# BootCircuit.net
KiCad netlist of a schematic drawn in Altium Designer
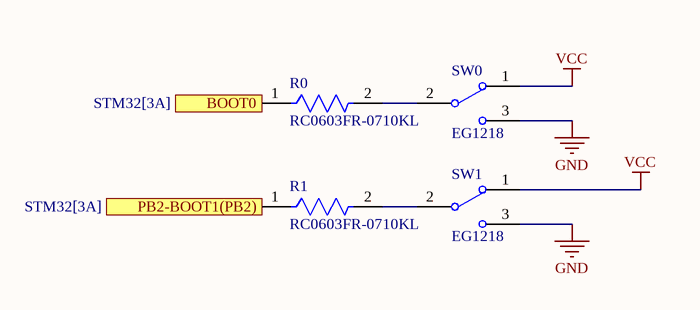
[diagram p0: BootCircuit.SchDoc]

(export (version "E")
  (design (tool "Eeschema 10.0.6"))
  (components
    (comp (ref "R0")
      (value "RC0603FR-0710KL")
      (footprint "FP-RC0603-0_55-IPC_C")
      (description "RES 10K OHM 1% 1/10W 0603")
      (fields (field (name "TOLERANCE") "1%"))
      (libsource (lib "Altium Content Vault") (part "1029c3af85768c4190bb7ad29bc67b5"))
    )
    (comp (ref "R1")
      (value "RC0603FR-0710KL")
      (footprint "FP-RC0603-0_55-IPC_C")
      (description "RES 10K OHM 1% 1/10W 0603")
      (fields (field (name "TOLERANCE") "1%"))
      (libsource (lib "Altium Content Vault") (part "1029c3af85768c4190bb7ad29bc67b5"))
    )
    (comp (ref "SW0")
      (value "EG1218")
      (footprint "ESWI-EG1218_V")
      (description "Slide Switch, 500 V, -20 to 70 degC, 3-Pin THD, RoHS")
      (libsource (lib "Altium Content Vault") (part "SW-SPDT-3_B"))
    )
    (comp (ref "SW1")
      (value "EG1218")
      (footprint "ESWI-EG1218_V")
      (description "Slide Switch, 500 V, -20 to 70 degC, 3-Pin THD, RoHS")
      (libsource (lib "Altium Content Vault") (part "SW-SPDT-3_B"))
    )
  )
  (nets
    (net (code "1") (name "/BOOT0") (class "Default")
      (node (ref "R0") (pin "1") (pinfunction "1_1") (pintype "passive"))
    )
    (net (code "2") (name "/PB2-BOOT1(PB2)") (class "Default")
      (node (ref "R1") (pin "1") (pinfunction "1_1") (pintype "passive"))
    )
    (net (code "3") (name "GND") (class "Default")
      (node (ref "SW0") (pin "3") (pinfunction "3_3") (pintype "passive"))
      (node (ref "SW1") (pin "3") (pinfunction "3_3") (pintype "passive"))
    )
    (net (code "4") (name "Net-(SW0-COM)") (class "Default")
      (node (ref "R0") (pin "2") (pinfunction "2_2") (pintype "passive"))
      (node (ref "SW0") (pin "2") (pinfunction "COM_2") (pintype "passive"))
    )
    (net (code "5") (name "Net-(SW1-COM)") (class "Default")
      (node (ref "R1") (pin "2") (pinfunction "2_2") (pintype "passive"))
      (node (ref "SW1") (pin "2") (pinfunction "COM_2") (pintype "passive"))
    )
    (net (code "6") (name "VCC") (class "Default")
      (node (ref "SW0") (pin "1") (pinfunction "1_1") (pintype "passive"))
      (node (ref "SW1") (pin "1") (pinfunction "1_1") (pintype "passive"))
    )
  )
)
